# 10_CAN_BUS.net
KiCad netlist of a schematic drawn in Altium Designer
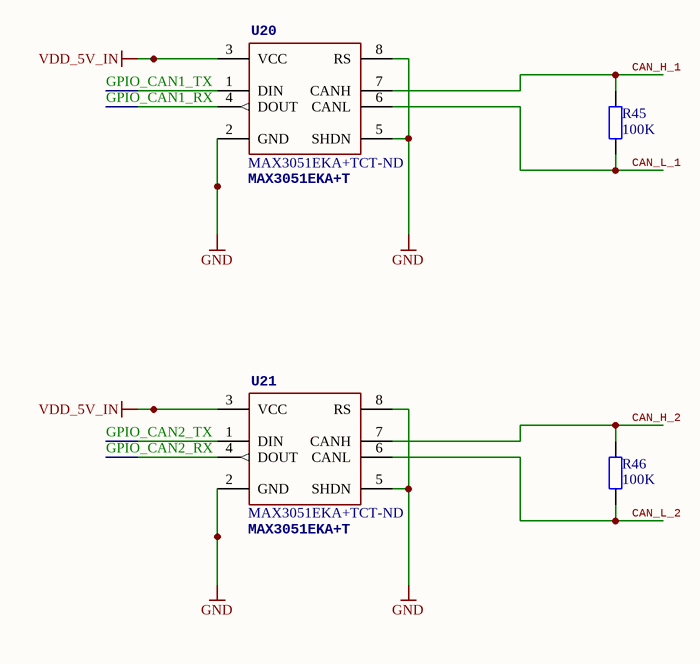
[diagram p0: 10_CAN_BUS.SchDoc]

(export (version "E")
  (design (tool "Eeschema 10.0.6"))
  (components
    (comp (ref "R45")
      (value "100K")
      (description "Resistor")
      (fields (field (name "PUBLISHER") "Altium Limited"))
      (libsource (lib "Miscellaneous Devices") (part "Res2"))
    )
    (comp (ref "R46")
      (value "100K")
      (description "Resistor")
      (fields (field (name "PUBLISHER") "Altium Limited"))
      (libsource (lib "Miscellaneous Devices") (part "Res2"))
    )
    (comp (ref "U20")
      (value "MAX3051EKA+T")
      (footprint "SOT23-8")
      (description "IC TXRX CAN 1MBPS SOT23-8")
      (fields
        (field (name "SUPPLIER PART NUMBER 1") "MAX3051EKA+TCT-ND")
        (field (name "3DR_PARTNO") "ECM0831")
      )
      (libsource (lib "pixhawk2") (part "MAX3051MAX3051EKA"))
    )
    (comp (ref "U21")
      (value "MAX3051EKA+T")
      (footprint "SOT23-8")
      (description "IC TXRX CAN 1MBPS SOT23-8")
      (fields
        (field (name "SUPPLIER PART NUMBER 1") "MAX3051EKA+TCT-ND")
        (field (name "3DR_PARTNO") "ECM0831")
      )
      (libsource (lib "pixhawk2") (part "MAX3051MAX3051EKA"))
    )
  )
  (nets
    (net (code "1") (name "/CAN_H_1") (class "Default")
      (node (ref "R45") (pin "1") (pinfunction "1_1") (pintype "passive"))
      (node (ref "U20") (pin "7") (pinfunction "CANH_7") (pintype "passive"))
    )
    (net (code "2") (name "/CAN_H_2") (class "Default")
      (node (ref "R46") (pin "1") (pinfunction "1_1") (pintype "passive"))
      (node (ref "U21") (pin "7") (pinfunction "CANH_7") (pintype "passive"))
    )
    (net (code "3") (name "/CAN_L_1") (class "Default")
      (node (ref "R45") (pin "2") (pinfunction "2_2") (pintype "passive"))
      (node (ref "U20") (pin "6") (pinfunction "CANL_6") (pintype "passive"))
    )
    (net (code "4") (name "/CAN_L_2") (class "Default")
      (node (ref "R46") (pin "2") (pinfunction "2_2") (pintype "passive"))
      (node (ref "U21") (pin "6") (pinfunction "CANL_6") (pintype "passive"))
    )
    (net (code "5") (name "/GPIO_CAN1_RX") (class "Default")
      (node (ref "U20") (pin "4") (pinfunction "DOUT_4") (pintype "output"))
    )
    (net (code "6") (name "/GPIO_CAN1_TX") (class "Default")
      (node (ref "U20") (pin "1") (pinfunction "DIN_1") (pintype "passive"))
    )
    (net (code "7") (name "/GPIO_CAN2_RX") (class "Default")
      (node (ref "U21") (pin "4") (pinfunction "DOUT_4") (pintype "output"))
    )
    (net (code "8") (name "/GPIO_CAN2_TX") (class "Default")
      (node (ref "U21") (pin "1") (pinfunction "DIN_1") (pintype "passive"))
    )
    (net (code "9") (name "GND") (class "Default")
      (node (ref "U20") (pin "2") (pinfunction "GND_2") (pintype "open_emitter"))
      (node (ref "U20") (pin "5") (pinfunction "SHDN_5") (pintype "passive"))
      (node (ref "U20") (pin "8") (pinfunction "RS_8") (pintype "passive"))
      (node (ref "U21") (pin "2") (pinfunction "GND_2") (pintype "open_emitter"))
      (node (ref "U21") (pin "5") (pinfunction "SHDN_5") (pintype "passive"))
      (node (ref "U21") (pin "8") (pinfunction "RS_8") (pintype "passive"))
    )
    (net (code "10") (name "VDD_5V_IN") (class "Default")
      (node (ref "U20") (pin "3") (pinfunction "VCC_3") (pintype "passive"))
      (node (ref "U21") (pin "3") (pinfunction "VCC_3") (pintype "passive"))
    )
  )
)
